# LED_chaser.net
KiCad netlist of a schematic drawn in Altium Designer
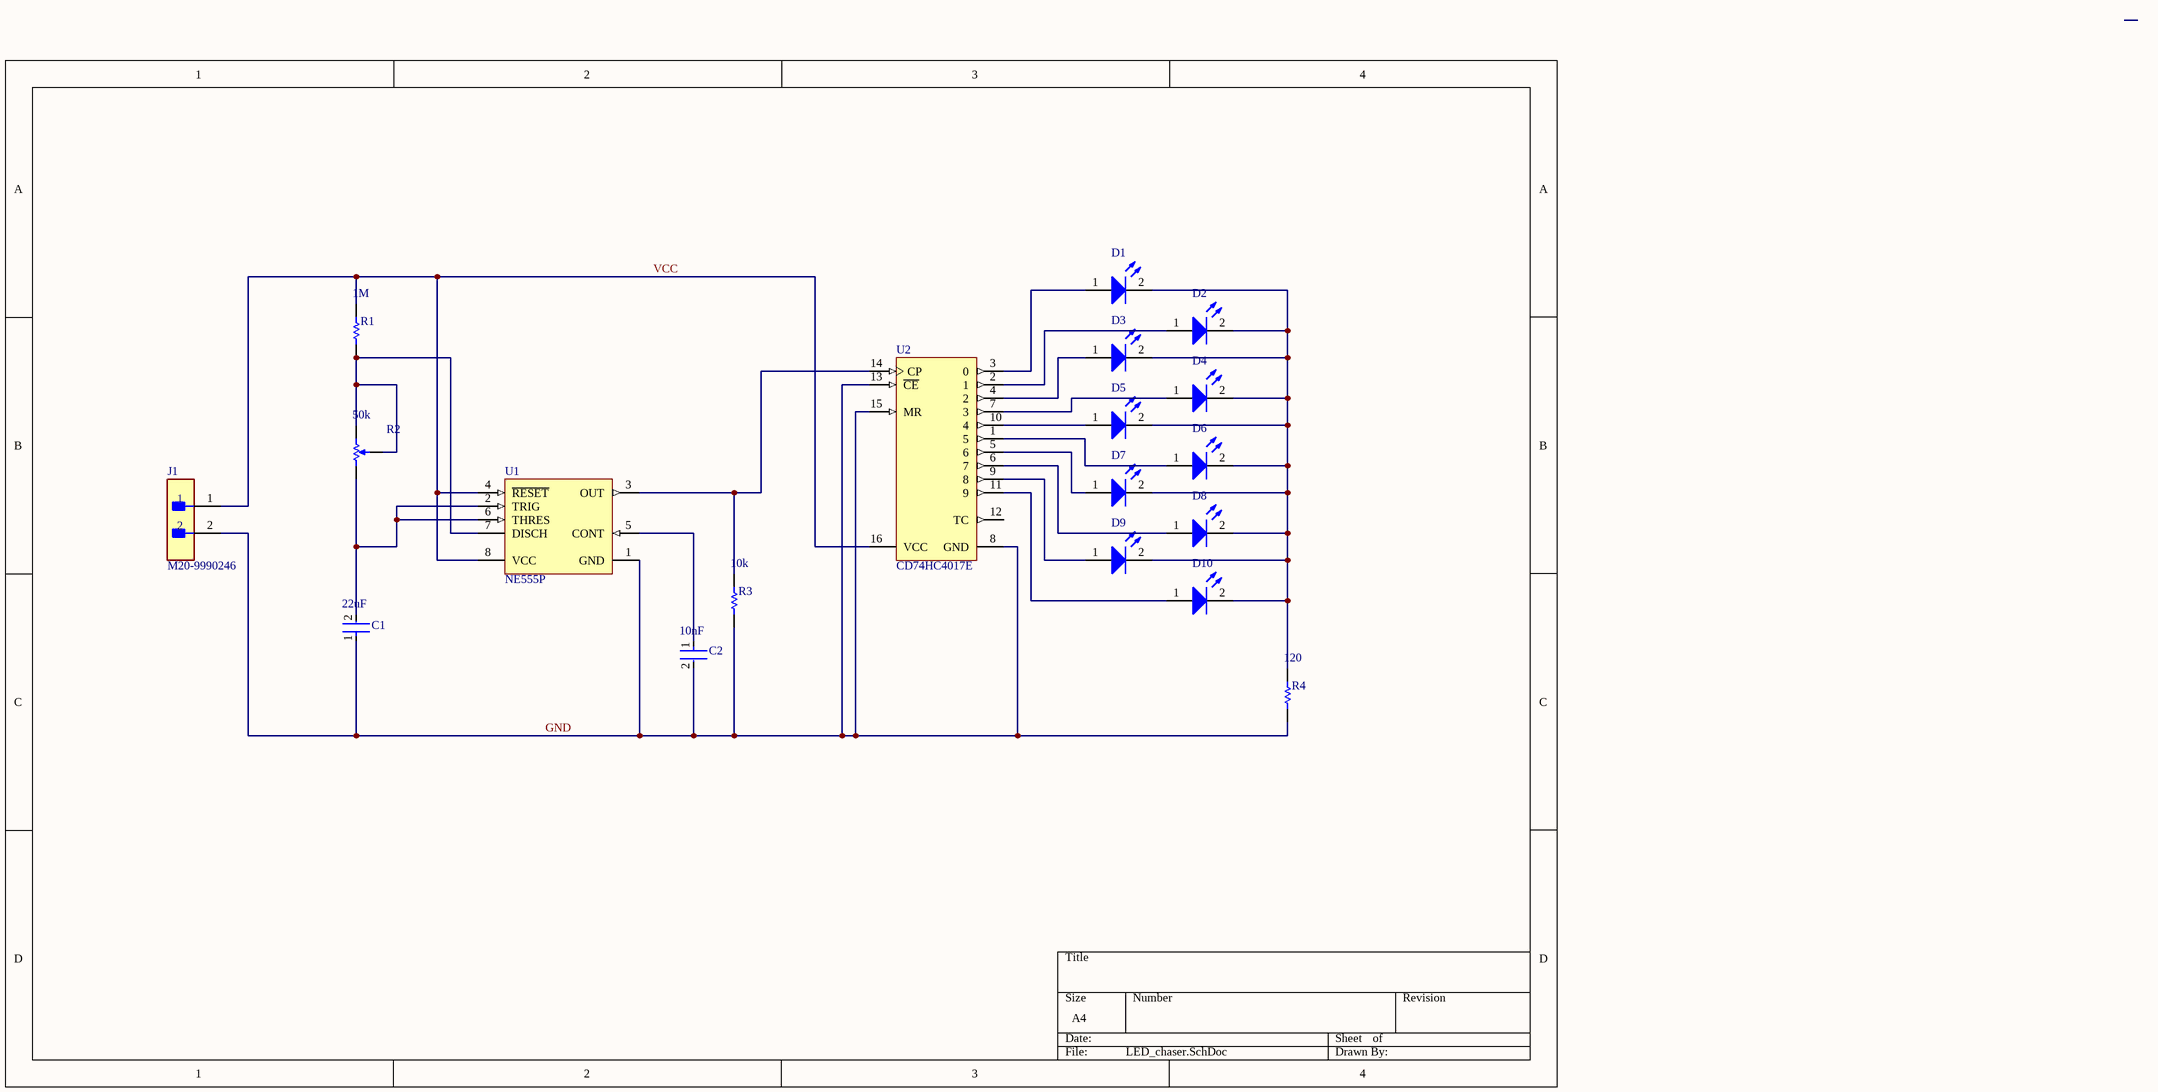
[diagram p0: LED_chaser.SchDoc]

(export (version "E")
  (design (tool "Eeschema 10.0.6"))
  (components
    (comp (ref "C1")
      (value "RCER71E226MWM1H03A")
      (footprint "FP-RCEWM1-MFG")
      (description "CAP CER 22UF 25V X7R RADIAL")
      (fields (field (name "CAPACITANCE") "22uF") (field (name "TOLERANCE") "20%"))
      (libsource (lib "Altium Content Vault") (part "02cd4be3c70576c341d710602a673aa"))
    )
    (comp (ref "C2")
      (value "RCER71H103K0K1H03B")
      (footprint "FP-RCE0K1-MFG")
      (description "Cap Ceramic 10nF 50V X7R ±10% Radial 5mm +125°C Automotive Bulk")
      (fields (field (name "CAPACITANCE") "10nF") (field (name "TOLERANCE") "10%"))
      (libsource (lib "Altium Content Vault") (part "b4654b650e69147ec39a6b967a45e02"))
    )
    (comp (ref "D1")
      (value "151051BS04000")
      (footprint "WL-TMRC_D5.9H8.7")
      (libsource (lib "Altium Content Vault") (part "LED_Blue_1A-2K"))
    )
    (comp (ref "D2")
      (value "151051BS04000")
      (footprint "WL-TMRC_D5.9H8.7")
      (libsource (lib "Altium Content Vault") (part "LED_Blue_1A-2K"))
    )
    (comp (ref "D3")
      (value "151051BS04000")
      (footprint "WL-TMRC_D5.9H8.7")
      (libsource (lib "Altium Content Vault") (part "LED_Blue_1A-2K"))
    )
    (comp (ref "D4")
      (value "151051BS04000")
      (footprint "WL-TMRC_D5.9H8.7")
      (libsource (lib "Altium Content Vault") (part "LED_Blue_1A-2K"))
    )
    (comp (ref "D5")
      (value "151051BS04000")
      (footprint "WL-TMRC_D5.9H8.7")
      (libsource (lib "Altium Content Vault") (part "LED_Blue_1A-2K"))
    )
    (comp (ref "D6")
      (value "151051BS04000")
      (footprint "WL-TMRC_D5.9H8.7")
      (libsource (lib "Altium Content Vault") (part "LED_Blue_1A-2K"))
    )
    (comp (ref "D7")
      (value "151051BS04000")
      (footprint "WL-TMRC_D5.9H8.7")
      (libsource (lib "Altium Content Vault") (part "LED_Blue_1A-2K"))
    )
    (comp (ref "D8")
      (value "151051BS04000")
      (footprint "WL-TMRC_D5.9H8.7")
      (libsource (lib "Altium Content Vault") (part "LED_Blue_1A-2K"))
    )
    (comp (ref "D9")
      (value "151051BS04000")
      (footprint "WL-TMRC_D5.9H8.7")
      (libsource (lib "Altium Content Vault") (part "LED_Blue_1A-2K"))
    )
    (comp (ref "D10")
      (value "151051BS04000")
      (footprint "WL-TMRC_D5.9H8.7")
      (libsource (lib "Altium Content Vault") (part "LED_Blue_1A-2K"))
    )
    (comp (ref "J1")
      (value "M20-9990246")
      (footprint "FP-M20-9990246-MFG")
      (description "Connector Header Through Hole 2 position 0.100\" (2.54mm)")
      (fields (field (name "OCTOPART") "https://octopart.com/m20-9990246-harwin-2590635"))
      (libsource (lib "Altium Content Vault") (part "3bc925449376181038e59eaffc5286c"))
    )
    (comp (ref "R1")
      (value "MFR-25FBF52-1M")
      (footprint "RESA60-630X240")
      (description "Axial Resistor, 1 MOhm, +/- 1%, 250 mW, -55 to 155 degC, 2-Pin THD, RoHS, Bulk")
      (fields (field (name "RESISTANCE") "1M") (field (name "TOLERANCE") "1%"))
      (libsource (lib "Altium Content Vault") (part "RES-2"))
    )
    (comp (ref "R2")
      (value "3313J-1-503E")
      (footprint "BOUR-3313J-1_V")
      (fields (field (name "MANUFACTURER") "Bourns") (field (name "TRACK RESISTANCE") "50k"))
      (libsource (lib "Altium Content Vault") (part "RES-ADJ-3_A"))
    )
    (comp (ref "R3")
      (value "OD103JE")
      (footprint "OMTE-RES7X2.5-2")
      (fields
        (field (name "RESISTANCE (OHMS)") "10k")
        (field (name "TOLERANCE") "±5%")
        (field (name "MANUFACTURER") "Ohmite")
      )
      (libsource (lib "Altium Content Vault") (part "RES-2"))
    )
    (comp (ref "R4")
      (value "OD103JE")
      (footprint "OMTE-RES7X2.5-2")
      (fields
        (field (name "RESISTANCE (OHMS)") "120")
        (field (name "TOLERANCE") "±5%")
        (field (name "MANUFACTURER") "Ohmite")
      )
      (libsource (lib "Altium Content Vault") (part "RES-2"))
    )
    (comp (ref "U1")
      (value "NE555P")
      (footprint "P0008A")
      (description "Precision Timer, 4.5 to 16 V, 0 to 70 degC, 8-Pin DIP, Pb-Free, Tube")
      (fields (field (name "MANUFACTURER") "TexasInstruments"))
      (libsource (lib "Altium Content Vault") (part "TI-NE555-P8"))
    )
    (comp (ref "U2")
      (value "CD74HC4017E")
      (footprint "N0016A")
      (description "High Speed CMOS Logic Decade Counter/Divider with 10 Decoded Outputs, N0016A, TUBE")
      (fields
        (field (name "GENERIC PART NUMBER") "CD74HC4017")
        (field (name "MANUFACTURER") "Texas Instruments")
      )
      (libsource (lib "Altium Content Vault") (part "TI-CD74HC4017-16"))
    )
  )
  (nets
    (net (code "1") (name "/GND") (class "Default")
      (node (ref "C1") (pin "1") (pinfunction "1_1") (pintype "passive"))
      (node (ref "C2") (pin "2") (pinfunction "2_2") (pintype "passive"))
      (node (ref "J1") (pin "2") (pinfunction "2_2") (pintype "passive"))
      (node (ref "R3") (pin "1") (pinfunction "1_1") (pintype "passive"))
      (node (ref "R4") (pin "1") (pinfunction "1_1") (pintype "passive"))
      (node (ref "U1") (pin "1") (pinfunction "GND_1") (pintype "power_in"))
      (node (ref "U2") (pin "13") (pinfunction "~{CE}_13") (pintype "input"))
      (node (ref "U2") (pin "15") (pinfunction "MR_15") (pintype "input"))
      (node (ref "U2") (pin "8") (pinfunction "GND_8") (pintype "power_in"))
    )
    (net (code "2") (name "/VCC") (class "Default")
      (node (ref "J1") (pin "1") (pinfunction "1_1") (pintype "passive"))
      (node (ref "R1") (pin "2") (pinfunction "2_2") (pintype "passive"))
      (node (ref "U1") (pin "4") (pinfunction "~{RESET}_4") (pintype "input"))
      (node (ref "U1") (pin "8") (pinfunction "VCC_8") (pintype "power_in"))
      (node (ref "U2") (pin "16") (pinfunction "VCC_16") (pintype "power_in"))
    )
    (net (code "3") (name "Net-(D1-A)") (class "Default")
      (node (ref "D1") (pin "1") (pinfunction "A_1") (pintype "passive"))
      (node (ref "U2") (pin "3") (pinfunction "0_3") (pintype "output"))
    )
    (net (code "4") (name "Net-(D1-K)") (class "Default")
      (node (ref "D1") (pin "2") (pinfunction "K_2") (pintype "passive"))
      (node (ref "D10") (pin "2") (pinfunction "K_2") (pintype "passive"))
      (node (ref "D2") (pin "2") (pinfunction "K_2") (pintype "passive"))
      (node (ref "D3") (pin "2") (pinfunction "K_2") (pintype "passive"))
      (node (ref "D4") (pin "2") (pinfunction "K_2") (pintype "passive"))
      (node (ref "D5") (pin "2") (pinfunction "K_2") (pintype "passive"))
      (node (ref "D6") (pin "2") (pinfunction "K_2") (pintype "passive"))
      (node (ref "D7") (pin "2") (pinfunction "K_2") (pintype "passive"))
      (node (ref "D8") (pin "2") (pinfunction "K_2") (pintype "passive"))
      (node (ref "D9") (pin "2") (pinfunction "K_2") (pintype "passive"))
      (node (ref "R4") (pin "2") (pinfunction "2_2") (pintype "passive"))
    )
    (net (code "5") (name "Net-(D2-A)") (class "Default")
      (node (ref "D2") (pin "1") (pinfunction "A_1") (pintype "passive"))
      (node (ref "U2") (pin "2") (pinfunction "1_2") (pintype "output"))
    )
    (net (code "6") (name "Net-(D3-A)") (class "Default")
      (node (ref "D3") (pin "1") (pinfunction "A_1") (pintype "passive"))
      (node (ref "U2") (pin "4") (pinfunction "2_4") (pintype "output"))
    )
    (net (code "7") (name "Net-(D4-A)") (class "Default")
      (node (ref "D4") (pin "1") (pinfunction "A_1") (pintype "passive"))
      (node (ref "U2") (pin "7") (pinfunction "3_7") (pintype "output"))
    )
    (net (code "8") (name "Net-(D5-A)") (class "Default")
      (node (ref "D5") (pin "1") (pinfunction "A_1") (pintype "passive"))
      (node (ref "U2") (pin "10") (pinfunction "4_10") (pintype "output"))
    )
    (net (code "9") (name "Net-(D6-A)") (class "Default")
      (node (ref "D6") (pin "1") (pinfunction "A_1") (pintype "passive"))
      (node (ref "U2") (pin "1") (pinfunction "5_1") (pintype "output"))
    )
    (net (code "10") (name "Net-(D7-A)") (class "Default")
      (node (ref "D7") (pin "1") (pinfunction "A_1") (pintype "passive"))
      (node (ref "U2") (pin "5") (pinfunction "6_5") (pintype "output"))
    )
    (net (code "11") (name "Net-(D8-A)") (class "Default")
      (node (ref "D8") (pin "1") (pinfunction "A_1") (pintype "passive"))
      (node (ref "U2") (pin "6") (pinfunction "7_6") (pintype "output"))
    )
    (net (code "12") (name "Net-(D9-A)") (class "Default")
      (node (ref "D9") (pin "1") (pinfunction "A_1") (pintype "passive"))
      (node (ref "U2") (pin "9") (pinfunction "8_9") (pintype "output"))
    )
    (net (code "13") (name "Net-(D10-A)") (class "Default")
      (node (ref "D10") (pin "1") (pinfunction "A_1") (pintype "passive"))
      (node (ref "U2") (pin "11") (pinfunction "9_11") (pintype "output"))
    )
    (net (code "14") (name "Net-(U1-CONT)") (class "Default")
      (node (ref "C2") (pin "1") (pinfunction "1_1") (pintype "passive"))
      (node (ref "U1") (pin "5") (pinfunction "CONT_5") (pintype "input"))
    )
    (net (code "15") (name "Net-(U1-DISCH)") (class "Default")
      (node (ref "R1") (pin "1") (pinfunction "1_1") (pintype "passive"))
      (node (ref "R2") (pin "2") (pinfunction "2_2") (pintype "passive"))
      (node (ref "R2") (pin "3") (pinfunction "3_3") (pintype "passive"))
      (node (ref "U1") (pin "7") (pinfunction "DISCH_7") (pintype "open_collector"))
    )
    (net (code "16") (name "Net-(U1-OUT)") (class "Default")
      (node (ref "R3") (pin "2") (pinfunction "2_2") (pintype "passive"))
      (node (ref "U1") (pin "3") (pinfunction "OUT_3") (pintype "output"))
      (node (ref "U2") (pin "14") (pinfunction "CP_14") (pintype "input"))
    )
    (net (code "17") (name "Net-(U1-THRES)") (class "Default")
      (node (ref "C1") (pin "2") (pinfunction "2_2") (pintype "passive"))
      (node (ref "R2") (pin "1") (pinfunction "1_1") (pintype "passive"))
      (node (ref "U1") (pin "2") (pinfunction "TRIG_2") (pintype "input"))
      (node (ref "U1") (pin "6") (pinfunction "THRES_6") (pintype "input"))
    )
    (net (code "18") (name "unconnected-(U2-TC-Pad12)") (class "Default")
      (node (ref "U2") (pin "12") (pinfunction "TC_12") (pintype "output"))
    )
  )
)
